# PCBSCH.net
KiCad netlist of a schematic drawn in EAGLE
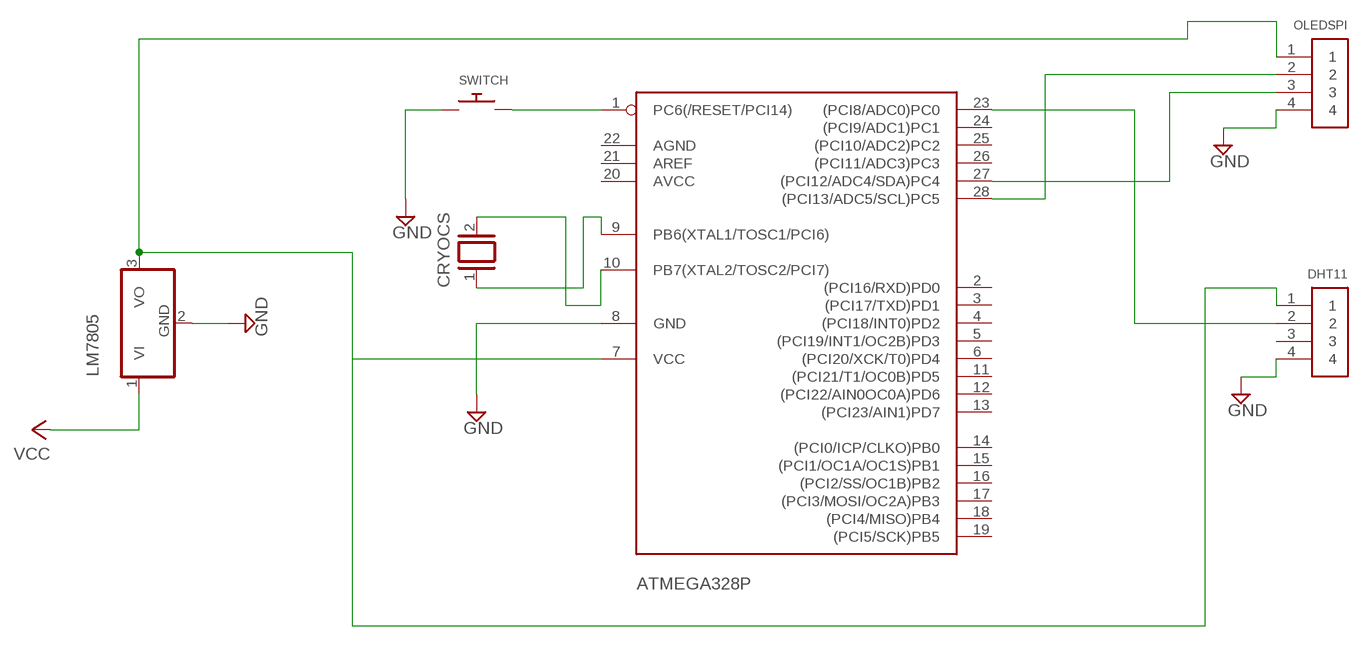
[diagram p0: schematic, sheet 1]

(export (version "E")
  (design (tool "Eeschema 10.0.6"))
  (components
    (comp (ref "ATMEGA328P")
      (value "ATMEGA328PROUND")
      (footprint "eagle-import:DIL28-3-ROUND")
      (libsource (lib "eagle-import") (part "ATMEGA328PROUND"))
    )
    (comp (ref "CRYOCS")
      (value "XTAL/S")
      (footprint "eagle-import:QS")
      (libsource (lib "eagle-import") (part "XTAL/S"))
    )
    (comp (ref "DHT11")
      (value "1X4-BIG")
      (footprint "eagle-import:1X04-BIG")
      (libsource (lib "eagle-import") (part "1X4-BIG"))
    )
    (comp (ref "LM7805")
      (value "7805TV")
      (footprint "eagle-import:TO220V")
      (libsource (lib "eagle-import") (part "78TV05"))
    )
    (comp (ref "OLEDSPI")
      (value "1X4-BIG")
      (footprint "eagle-import:1X04-BIG")
      (libsource (lib "eagle-import") (part "1X4-BIG"))
    )
    (comp (ref "SWITCH")
      (value "SWITCH_PUSHBUTTONSOFTTOUCHSMD_SJ")
      (footprint "eagle-import:PUSHBUTTON_SMD_SJ")
      (libsource (lib "eagle-import") (part "SWITCH_PUSHBUTTONSOFTTOUCHSMD_SJ"))
    )
  )
  (nets
    (net (code "1") (name "GND") (class "Default")
      (node (ref "ATMEGA328P") (pin "8") (pinfunction "GND_8") (pintype "bidirectional"))
      (node (ref "DHT11") (pin "4") (pinfunction "4_4") (pintype "bidirectional"))
      (node (ref "LM7805") (pin "2") (pinfunction "GND_2") (pintype "passive"))
      (node (ref "OLEDSPI") (pin "4") (pinfunction "4_4") (pintype "bidirectional"))
      (node (ref "SWITCH") (pin "P$1") (pinfunction "P$1_P$1") (pintype "passive"))
    )
    (net (code "2") (name "Net-(ATMEGA328P-(PCI8{slash}ADC0)PC0)") (class "Default")
      (node (ref "ATMEGA328P") (pin "23") (pinfunction "(PCI8/ADC0)PC0_23") (pintype "bidirectional"))
      (node (ref "DHT11") (pin "2") (pinfunction "2_2") (pintype "bidirectional"))
    )
    (net (code "3") (name "Net-(ATMEGA328P-(PCI12{slash}ADC4{slash}SDA)PC4)") (class "Default")
      (node (ref "ATMEGA328P") (pin "27") (pinfunction "(PCI12/ADC4/SDA)PC4_27") (pintype "bidirectional"))
      (node (ref "OLEDSPI") (pin "3") (pinfunction "3_3") (pintype "bidirectional"))
    )
    (net (code "4") (name "Net-(ATMEGA328P-(PCI13{slash}ADC5{slash}SCL)PC5)") (class "Default")
      (node (ref "ATMEGA328P") (pin "28") (pinfunction "(PCI13/ADC5/SCL)PC5_28") (pintype "bidirectional"))
      (node (ref "OLEDSPI") (pin "2") (pinfunction "2_2") (pintype "bidirectional"))
    )
    (net (code "5") (name "Net-(ATMEGA328P-PB6(XTAL1{slash}TOSC1{slash}PCI6))") (class "Default")
      (node (ref "ATMEGA328P") (pin "9") (pinfunction "PB6(XTAL1/TOSC1/PCI6)_9") (pintype "bidirectional"))
      (node (ref "CRYOCS") (pin "1") (pinfunction "1_1") (pintype "passive"))
    )
    (net (code "6") (name "Net-(ATMEGA328P-PB7(XTAL2{slash}TOSC2{slash}PCI7))") (class "Default")
      (node (ref "ATMEGA328P") (pin "10") (pinfunction "PB7(XTAL2/TOSC2/PCI7)_10") (pintype "bidirectional"))
      (node (ref "CRYOCS") (pin "2") (pinfunction "2_2") (pintype "passive"))
    )
    (net (code "7") (name "Net-(ATMEGA328P-PC6({slash}RESET{slash}PCI14))") (class "Default")
      (node (ref "ATMEGA328P") (pin "1") (pinfunction "PC6(/RESET/PCI14)_1") (pintype "bidirectional"))
      (node (ref "SWITCH") (pin "P$2") (pinfunction "P$2_P$2") (pintype "passive"))
    )
    (net (code "8") (name "Net-(ATMEGA328P-VCC)") (class "Default")
      (node (ref "ATMEGA328P") (pin "7") (pinfunction "VCC_7") (pintype "bidirectional"))
      (node (ref "DHT11") (pin "1") (pinfunction "1_1") (pintype "bidirectional"))
      (node (ref "LM7805") (pin "3") (pinfunction "VO_3") (pintype "passive"))
      (node (ref "OLEDSPI") (pin "1") (pinfunction "1_1") (pintype "bidirectional"))
    )
    (net (code "9") (name "VCC") (class "Default")
      (node (ref "LM7805") (pin "1") (pinfunction "VI_1") (pintype "input"))
    )
    (net (code "10") (name "unconnected-(ATMEGA328P-(PCI0{slash}ICP{slash}CLKO)PB0-Pad14)") (class "Default")
      (node (ref "ATMEGA328P") (pin "14") (pinfunction "(PCI0/ICP/CLKO)PB0_14") (pintype "bidirectional"))
    )
    (net (code "11") (name "unconnected-(ATMEGA328P-(PCI1{slash}OC1A{slash}OC1S)PB1-Pad15)") (class "Default")
      (node (ref "ATMEGA328P") (pin "15") (pinfunction "(PCI1/OC1A/OC1S)PB1_15") (pintype "bidirectional"))
    )
    (net (code "12") (name "unconnected-(ATMEGA328P-(PCI2{slash}SS{slash}OC1B)PB2-Pad16)") (class "Default")
      (node (ref "ATMEGA328P") (pin "16") (pinfunction "(PCI2/SS/OC1B)PB2_16") (pintype "bidirectional"))
    )
    (net (code "13") (name "unconnected-(ATMEGA328P-(PCI3{slash}MOSI{slash}OC2A)PB3-Pad17)") (class "Default")
      (node (ref "ATMEGA328P") (pin "17") (pinfunction "(PCI3/MOSI/OC2A)PB3_17") (pintype "bidirectional"))
    )
    (net (code "14") (name "unconnected-(ATMEGA328P-(PCI4{slash}MISO)PB4-Pad18)") (class "Default")
      (node (ref "ATMEGA328P") (pin "18") (pinfunction "(PCI4/MISO)PB4_18") (pintype "bidirectional"))
    )
    (net (code "15") (name "unconnected-(ATMEGA328P-(PCI5{slash}SCK)PB5-Pad19)") (class "Default")
      (node (ref "ATMEGA328P") (pin "19") (pinfunction "(PCI5/SCK)PB5_19") (pintype "bidirectional"))
    )
    (net (code "16") (name "unconnected-(ATMEGA328P-(PCI9{slash}ADC1)PC1-Pad24)") (class "Default")
      (node (ref "ATMEGA328P") (pin "24") (pinfunction "(PCI9/ADC1)PC1_24") (pintype "bidirectional"))
    )
    (net (code "17") (name "unconnected-(ATMEGA328P-(PCI10{slash}ADC2)PC2-Pad25)") (class "Default")
      (node (ref "ATMEGA328P") (pin "25") (pinfunction "(PCI10/ADC2)PC2_25") (pintype "bidirectional"))
    )
    (net (code "18") (name "unconnected-(ATMEGA328P-(PCI11{slash}ADC3)PC3-Pad26)") (class "Default")
      (node (ref "ATMEGA328P") (pin "26") (pinfunction "(PCI11/ADC3)PC3_26") (pintype "bidirectional"))
    )
    (net (code "19") (name "unconnected-(ATMEGA328P-(PCI16{slash}RXD)PD0-Pad2)") (class "Default")
      (node (ref "ATMEGA328P") (pin "2") (pinfunction "(PCI16/RXD)PD0_2") (pintype "bidirectional"))
    )
    (net (code "20") (name "unconnected-(ATMEGA328P-(PCI17{slash}TXD)PD1-Pad3)") (class "Default")
      (node (ref "ATMEGA328P") (pin "3") (pinfunction "(PCI17/TXD)PD1_3") (pintype "bidirectional"))
    )
    (net (code "21") (name "unconnected-(ATMEGA328P-(PCI18{slash}INT0)PD2-Pad4)") (class "Default")
      (node (ref "ATMEGA328P") (pin "4") (pinfunction "(PCI18/INT0)PD2_4") (pintype "bidirectional"))
    )
    (net (code "22") (name "unconnected-(ATMEGA328P-(PCI19{slash}INT1{slash}OC2B)PD3-Pad5)") (class "Default")
      (node (ref "ATMEGA328P") (pin "5") (pinfunction "(PCI19/INT1/OC2B)PD3_5") (pintype "bidirectional"))
    )
    (net (code "23") (name "unconnected-(ATMEGA328P-(PCI20{slash}XCK{slash}T0)PD4-Pad6)") (class "Default")
      (node (ref "ATMEGA328P") (pin "6") (pinfunction "(PCI20/XCK/T0)PD4_6") (pintype "bidirectional"))
    )
    (net (code "24") (name "unconnected-(ATMEGA328P-(PCI21{slash}T1{slash}OC0B)PD5-Pad11)") (class "Default")
      (node (ref "ATMEGA328P") (pin "11") (pinfunction "(PCI21/T1/OC0B)PD5_11") (pintype "bidirectional"))
    )
    (net (code "25") (name "unconnected-(ATMEGA328P-(PCI22{slash}AIN0OC0A)PD6-Pad12)") (class "Default")
      (node (ref "ATMEGA328P") (pin "12") (pinfunction "(PCI22/AIN0OC0A)PD6_12") (pintype "bidirectional"))
    )
    (net (code "26") (name "unconnected-(ATMEGA328P-(PCI23{slash}AIN1)PD7-Pad13)") (class "Default")
      (node (ref "ATMEGA328P") (pin "13") (pinfunction "(PCI23/AIN1)PD7_13") (pintype "bidirectional"))
    )
    (net (code "27") (name "unconnected-(ATMEGA328P-AGND-Pad22)") (class "Default")
      (node (ref "ATMEGA328P") (pin "22") (pinfunction "AGND_22") (pintype "bidirectional"))
    )
    (net (code "28") (name "unconnected-(ATMEGA328P-AREF-Pad21)") (class "Default")
      (node (ref "ATMEGA328P") (pin "21") (pinfunction "AREF_21") (pintype "bidirectional"))
    )
    (net (code "29") (name "unconnected-(ATMEGA328P-AVCC-Pad20)") (class "Default")
      (node (ref "ATMEGA328P") (pin "20") (pinfunction "AVCC_20") (pintype "bidirectional"))
    )
    (net (code "30") (name "unconnected-(DHT11-Pad3)") (class "Default")
      (node (ref "DHT11") (pin "3") (pinfunction "3_3") (pintype "bidirectional"))
    )
  )
)
